# DUCO_Miner_10D.net
KiCad netlist of a schematic drawn in EAGLE
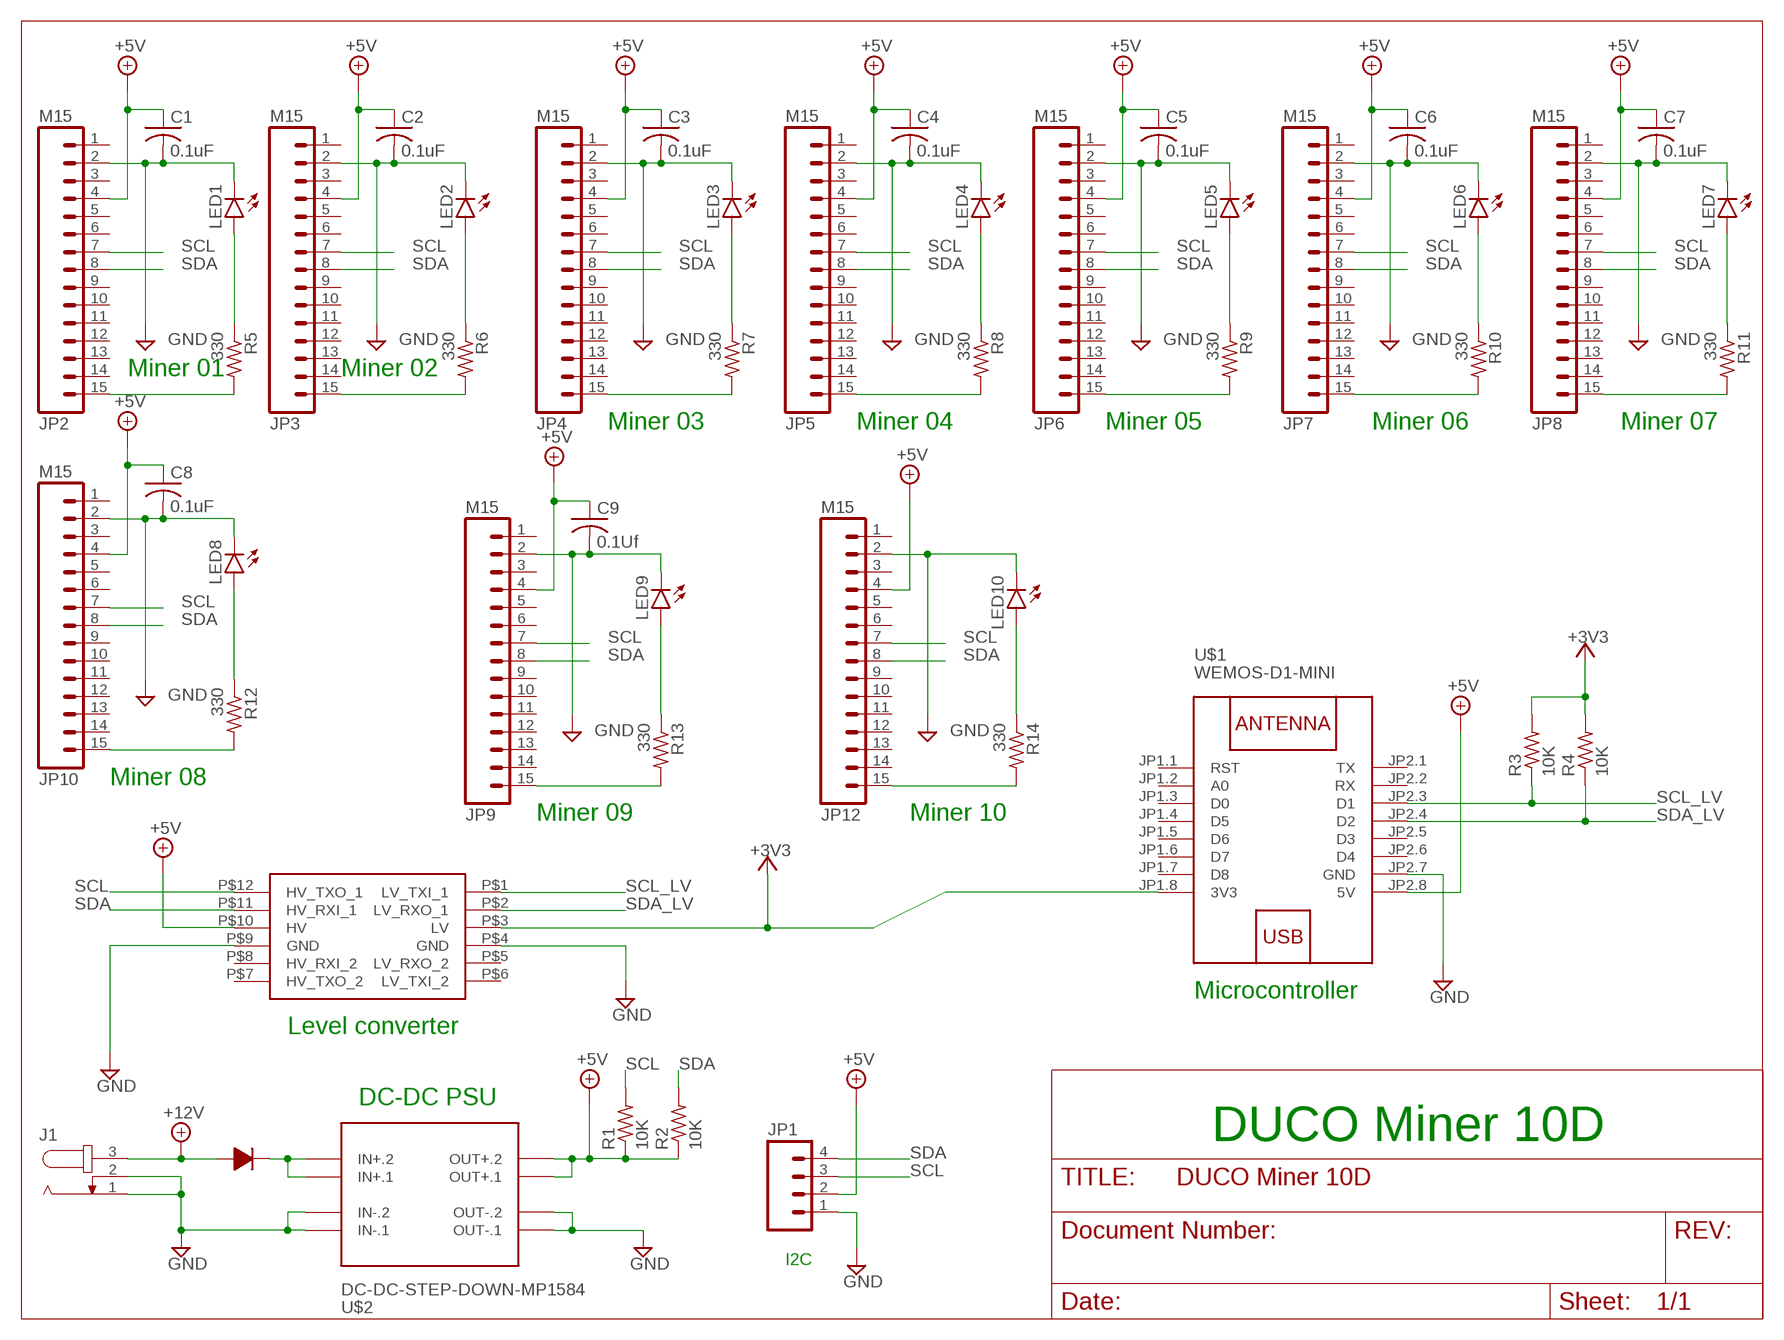
[diagram p0: schematic, sheet 1]

(export (version "E")
  (design (tool "Eeschema 10.0.6"))
  (components
    (comp (ref "C1")
      (value "0.1uF")
      (footprint "eagle-import:C025-025X050")
      (libsource (lib "eagle-import") (part "C-US025-025X050"))
    )
    (comp (ref "C2")
      (value "0.1uF")
      (footprint "eagle-import:C025-025X050")
      (libsource (lib "eagle-import") (part "C-US025-025X050"))
    )
    (comp (ref "C3")
      (value "0.1uF")
      (footprint "eagle-import:C025-025X050")
      (libsource (lib "eagle-import") (part "C-US025-025X050"))
    )
    (comp (ref "C4")
      (value "0.1uF")
      (footprint "eagle-import:C025-025X050")
      (libsource (lib "eagle-import") (part "C-US025-025X050"))
    )
    (comp (ref "C5")
      (value "0.1uF")
      (footprint "eagle-import:C025-025X050")
      (libsource (lib "eagle-import") (part "C-US025-025X050"))
    )
    (comp (ref "C6")
      (value "0.1uF")
      (footprint "eagle-import:C025-025X050")
      (libsource (lib "eagle-import") (part "C-US025-025X050"))
    )
    (comp (ref "C7")
      (value "0.1uF")
      (footprint "eagle-import:C025-025X050")
      (libsource (lib "eagle-import") (part "C-US025-025X050"))
    )
    (comp (ref "C8")
      (value "0.1uF")
      (footprint "eagle-import:C025-025X050")
      (libsource (lib "eagle-import") (part "C-US025-025X050"))
    )
    (comp (ref "C9")
      (value "0.1Uf")
      (footprint "eagle-import:C025-025X050")
      (libsource (lib "eagle-import") (part "C-US025-025X050"))
    )
    (comp (ref "J1")
      (value "JACK-PLUG1")
      (footprint "eagle-import:SPC4078")
      (libsource (lib "eagle-import") (part "JACK-PLUG1"))
    )
    (comp (ref "JP1")
      (value "M04PTH")
      (footprint "eagle-import:1X04")
      (libsource (lib "eagle-import") (part "M04PTH"))
    )
    (comp (ref "JP2")
      (value "M15")
      (footprint "eagle-import:1X15")
      (libsource (lib "eagle-import") (part "M15"))
    )
    (comp (ref "JP3")
      (value "M15")
      (footprint "eagle-import:1X15")
      (libsource (lib "eagle-import") (part "M15"))
    )
    (comp (ref "JP4")
      (value "M15")
      (footprint "eagle-import:1X15")
      (libsource (lib "eagle-import") (part "M15"))
    )
    (comp (ref "JP5")
      (value "M15")
      (footprint "eagle-import:1X15")
      (libsource (lib "eagle-import") (part "M15"))
    )
    (comp (ref "JP6")
      (value "M15")
      (footprint "eagle-import:1X15")
      (libsource (lib "eagle-import") (part "M15"))
    )
    (comp (ref "JP7")
      (value "M15")
      (footprint "eagle-import:1X15")
      (libsource (lib "eagle-import") (part "M15"))
    )
    (comp (ref "JP8")
      (value "M15")
      (footprint "eagle-import:1X15")
      (libsource (lib "eagle-import") (part "M15"))
    )
    (comp (ref "JP9")
      (value "M15")
      (footprint "eagle-import:1X15")
      (libsource (lib "eagle-import") (part "M15"))
    )
    (comp (ref "JP10")
      (value "M15")
      (footprint "eagle-import:1X15")
      (libsource (lib "eagle-import") (part "M15"))
    )
    (comp (ref "JP12")
      (value "M15")
      (footprint "eagle-import:1X15")
      (libsource (lib "eagle-import") (part "M15"))
    )
    (comp (ref "LED1")
      (value "LED3MM")
      (footprint "eagle-import:LED3MM")
      (libsource (lib "eagle-import") (part "LED3MM"))
    )
    (comp (ref "LED2")
      (value "LED3MM")
      (footprint "eagle-import:LED3MM")
      (libsource (lib "eagle-import") (part "LED3MM"))
    )
    (comp (ref "LED3")
      (value "LED3MM")
      (footprint "eagle-import:LED3MM")
      (libsource (lib "eagle-import") (part "LED3MM"))
    )
    (comp (ref "LED4")
      (value "LED3MM")
      (footprint "eagle-import:LED3MM")
      (libsource (lib "eagle-import") (part "LED3MM"))
    )
    (comp (ref "LED5")
      (value "LED3MM")
      (footprint "eagle-import:LED3MM")
      (libsource (lib "eagle-import") (part "LED3MM"))
    )
    (comp (ref "LED6")
      (value "LED3MM")
      (footprint "eagle-import:LED3MM")
      (libsource (lib "eagle-import") (part "LED3MM"))
    )
    (comp (ref "LED7")
      (value "LED3MM")
      (footprint "eagle-import:LED3MM")
      (libsource (lib "eagle-import") (part "LED3MM"))
    )
    (comp (ref "LED8")
      (value "LED3MM")
      (footprint "eagle-import:LED3MM")
      (libsource (lib "eagle-import") (part "LED3MM"))
    )
    (comp (ref "LED9")
      (value "LED3MM")
      (footprint "eagle-import:LED3MM")
      (libsource (lib "eagle-import") (part "LED3MM"))
    )
    (comp (ref "LED10")
      (value "LED3MM")
      (footprint "eagle-import:LED3MM")
      (libsource (lib "eagle-import") (part "LED3MM"))
    )
    (comp (ref "R1")
      (value "10K")
      (footprint "eagle-import:0204_7")
      (libsource (lib "eagle-import") (part "rcl_334_R-US_0204/7"))
    )
    (comp (ref "R2")
      (value "10K")
      (footprint "eagle-import:0204_7")
      (libsource (lib "eagle-import") (part "rcl_334_R-US_0204/7"))
    )
    (comp (ref "R3")
      (value "10K")
      (footprint "eagle-import:0204_7")
      (libsource (lib "eagle-import") (part "rcl_334_R-US_0204/7"))
    )
    (comp (ref "R4")
      (value "10K")
      (footprint "eagle-import:0204_7")
      (libsource (lib "eagle-import") (part "rcl_334_R-US_0204/7"))
    )
    (comp (ref "R5")
      (value "330")
      (footprint "eagle-import:0204_7")
      (libsource (lib "eagle-import") (part "R-US_0204/7"))
    )
    (comp (ref "R6")
      (value "330")
      (footprint "eagle-import:0204_7")
      (libsource (lib "eagle-import") (part "R-US_0204/7"))
    )
    (comp (ref "R7")
      (value "330")
      (footprint "eagle-import:0204_7")
      (libsource (lib "eagle-import") (part "R-US_0204/7"))
    )
    (comp (ref "R8")
      (value "330")
      (footprint "eagle-import:0204_7")
      (libsource (lib "eagle-import") (part "R-US_0204/7"))
    )
    (comp (ref "R9")
      (value "330")
      (footprint "eagle-import:0204_7")
      (libsource (lib "eagle-import") (part "R-US_0204/7"))
    )
    (comp (ref "R10")
      (value "330")
      (footprint "eagle-import:0204_7")
      (libsource (lib "eagle-import") (part "R-US_0204/7"))
    )
    (comp (ref "R11")
      (value "330")
      (footprint "eagle-import:0204_7")
      (libsource (lib "eagle-import") (part "R-US_0204/7"))
    )
    (comp (ref "R12")
      (value "330")
      (footprint "eagle-import:0204_7")
      (libsource (lib "eagle-import") (part "R-US_0204/7"))
    )
    (comp (ref "R13")
      (value "330")
      (footprint "eagle-import:0204_7")
      (libsource (lib "eagle-import") (part "R-US_0204/7"))
    )
    (comp (ref "R14")
      (value "330")
      (footprint "eagle-import:0204_7")
      (libsource (lib "eagle-import") (part "R-US_0204/7"))
    )
    (comp (ref "U$1")
      (value "WEMOS-D1-MINI")
      (footprint "eagle-import:WEMOS-D1-MINI")
      (libsource (lib "eagle-import") (part "WEMOS-D1-MINI"))
    )
    (comp (ref "U$2")
      (value "DC-DC-STEP-DOWN-MP1584")
      (footprint "eagle-import:DC-DC-STEP-DOWN-MP1584")
      (libsource (lib "eagle-import") (part "DC-DC-STEP-DOWN-MP1584"))
    )
    (comp (ref "U$3")
      (value "LOGIC_LEVEL_CONVERTER")
      (footprint "eagle-import:LOGIC_LEVEL_CONVERTER")
      (libsource (lib "eagle-import") (part "LOGIC_LEVEL_CONVERTER"))
    )
    (comp (ref "U$4")
      (value "1N4001")
      (footprint "eagle-import:DIODE-12.70")
      (libsource (lib "eagle-import") (part "1N4001"))
    )
  )
  (nets
    (net (code "1") (name "+3V3") (class "Default")
      (node (ref "R3") (pin "2") (pinfunction "2_2") (pintype "passive"))
      (node (ref "R4") (pin "2") (pinfunction "2_2") (pintype "passive"))
      (node (ref "U$1") (pin "JP1.8") (pinfunction "3V3_JP1.8") (pintype "power_in"))
      (node (ref "U$3") (pin "P$3") (pinfunction "LV_P$3") (pintype "bidirectional"))
    )
    (net (code "2") (name "+5V") (class "Default")
      (node (ref "C1") (pin "1") (pinfunction "1_1") (pintype "passive"))
      (node (ref "C2") (pin "1") (pinfunction "1_1") (pintype "passive"))
      (node (ref "C3") (pin "1") (pinfunction "1_1") (pintype "passive"))
      (node (ref "C4") (pin "1") (pinfunction "1_1") (pintype "passive"))
      (node (ref "C5") (pin "1") (pinfunction "1_1") (pintype "passive"))
      (node (ref "C6") (pin "1") (pinfunction "1_1") (pintype "passive"))
      (node (ref "C7") (pin "1") (pinfunction "1_1") (pintype "passive"))
      (node (ref "C8") (pin "1") (pinfunction "1_1") (pintype "passive"))
      (node (ref "C9") (pin "1") (pinfunction "1_1") (pintype "passive"))
      (node (ref "JP1") (pin "2") (pinfunction "2_2") (pintype "passive"))
      (node (ref "JP10") (pin "4") (pinfunction "4_4") (pintype "passive"))
      (node (ref "JP12") (pin "4") (pinfunction "4_4") (pintype "passive"))
      (node (ref "JP2") (pin "4") (pinfunction "4_4") (pintype "passive"))
      (node (ref "JP3") (pin "4") (pinfunction "4_4") (pintype "passive"))
      (node (ref "JP4") (pin "4") (pinfunction "4_4") (pintype "passive"))
      (node (ref "JP5") (pin "4") (pinfunction "4_4") (pintype "passive"))
      (node (ref "JP6") (pin "4") (pinfunction "4_4") (pintype "passive"))
      (node (ref "JP7") (pin "4") (pinfunction "4_4") (pintype "passive"))
      (node (ref "JP8") (pin "4") (pinfunction "4_4") (pintype "passive"))
      (node (ref "JP9") (pin "4") (pinfunction "4_4") (pintype "passive"))
      (node (ref "R1") (pin "1") (pinfunction "1_1") (pintype "passive"))
      (node (ref "R2") (pin "1") (pinfunction "1_1") (pintype "passive"))
      (node (ref "U$1") (pin "JP2.8") (pinfunction "5V_JP2.8") (pintype "power_in"))
      (node (ref "U$2") (pin "OUT+.1") (pinfunction "OUT+.1_OUT+.1") (pintype "bidirectional"))
      (node (ref "U$2") (pin "OUT+.2") (pinfunction "OUT+.2_OUT+.2") (pintype "bidirectional"))
      (node (ref "U$3") (pin "P$10") (pinfunction "HV_P$10") (pintype "bidirectional"))
    )
    (net (code "3") (name "+12V") (class "Default")
      (node (ref "J1") (pin "3") (pinfunction "3_3") (pintype "passive"))
      (node (ref "U$4") (pin "P$1") (pinfunction "P$1_P$1") (pintype "passive"))
    )
    (net (code "4") (name "/SCL") (class "Default")
      (node (ref "JP1") (pin "3") (pinfunction "3_3") (pintype "passive"))
      (node (ref "JP10") (pin "7") (pinfunction "7_7") (pintype "passive"))
      (node (ref "JP12") (pin "7") (pinfunction "7_7") (pintype "passive"))
      (node (ref "JP2") (pin "7") (pinfunction "7_7") (pintype "passive"))
      (node (ref "JP3") (pin "7") (pinfunction "7_7") (pintype "passive"))
      (node (ref "JP4") (pin "7") (pinfunction "7_7") (pintype "passive"))
      (node (ref "JP5") (pin "7") (pinfunction "7_7") (pintype "passive"))
      (node (ref "JP6") (pin "7") (pinfunction "7_7") (pintype "passive"))
      (node (ref "JP7") (pin "7") (pinfunction "7_7") (pintype "passive"))
      (node (ref "JP8") (pin "7") (pinfunction "7_7") (pintype "passive"))
      (node (ref "JP9") (pin "7") (pinfunction "7_7") (pintype "passive"))
      (node (ref "R1") (pin "2") (pinfunction "2_2") (pintype "passive"))
      (node (ref "U$3") (pin "P$12") (pinfunction "HV_TXO_1_P$12") (pintype "bidirectional"))
    )
    (net (code "5") (name "/SCL_LV") (class "Default")
      (node (ref "R3") (pin "1") (pinfunction "1_1") (pintype "passive"))
      (node (ref "U$1") (pin "JP2.3") (pinfunction "D1_JP2.3") (pintype "bidirectional"))
      (node (ref "U$3") (pin "P$1") (pinfunction "LV_TXI_1_P$1") (pintype "bidirectional"))
    )
    (net (code "6") (name "/SDA") (class "Default")
      (node (ref "JP1") (pin "4") (pinfunction "4_4") (pintype "passive"))
      (node (ref "JP10") (pin "8") (pinfunction "8_8") (pintype "passive"))
      (node (ref "JP12") (pin "8") (pinfunction "8_8") (pintype "passive"))
      (node (ref "JP2") (pin "8") (pinfunction "8_8") (pintype "passive"))
      (node (ref "JP3") (pin "8") (pinfunction "8_8") (pintype "passive"))
      (node (ref "JP4") (pin "8") (pinfunction "8_8") (pintype "passive"))
      (node (ref "JP5") (pin "8") (pinfunction "8_8") (pintype "passive"))
      (node (ref "JP6") (pin "8") (pinfunction "8_8") (pintype "passive"))
      (node (ref "JP7") (pin "8") (pinfunction "8_8") (pintype "passive"))
      (node (ref "JP8") (pin "8") (pinfunction "8_8") (pintype "passive"))
      (node (ref "JP9") (pin "8") (pinfunction "8_8") (pintype "passive"))
      (node (ref "R2") (pin "2") (pinfunction "2_2") (pintype "passive"))
      (node (ref "U$3") (pin "P$11") (pinfunction "HV_RXI_1_P$11") (pintype "bidirectional"))
    )
    (net (code "7") (name "/SDA_LV") (class "Default")
      (node (ref "R4") (pin "1") (pinfunction "1_1") (pintype "passive"))
      (node (ref "U$1") (pin "JP2.4") (pinfunction "D2_JP2.4") (pintype "bidirectional"))
      (node (ref "U$3") (pin "P$2") (pinfunction "LV_RXO_1_P$2") (pintype "bidirectional"))
    )
    (net (code "8") (name "GND") (class "Default")
      (node (ref "C1") (pin "2") (pinfunction "2_2") (pintype "passive"))
      (node (ref "C2") (pin "2") (pinfunction "2_2") (pintype "passive"))
      (node (ref "C3") (pin "2") (pinfunction "2_2") (pintype "passive"))
      (node (ref "C4") (pin "2") (pinfunction "2_2") (pintype "passive"))
      (node (ref "C5") (pin "2") (pinfunction "2_2") (pintype "passive"))
      (node (ref "C6") (pin "2") (pinfunction "2_2") (pintype "passive"))
      (node (ref "C7") (pin "2") (pinfunction "2_2") (pintype "passive"))
      (node (ref "C8") (pin "2") (pinfunction "2_2") (pintype "passive"))
      (node (ref "C9") (pin "2") (pinfunction "2_2") (pintype "passive"))
      (node (ref "J1") (pin "1") (pinfunction "1_1") (pintype "passive"))
      (node (ref "J1") (pin "2") (pinfunction "2_2") (pintype "passive"))
      (node (ref "JP1") (pin "1") (pinfunction "1_1") (pintype "passive"))
      (node (ref "JP10") (pin "2") (pinfunction "2_2") (pintype "passive"))
      (node (ref "JP12") (pin "2") (pinfunction "2_2") (pintype "passive"))
      (node (ref "JP2") (pin "2") (pinfunction "2_2") (pintype "passive"))
      (node (ref "JP3") (pin "2") (pinfunction "2_2") (pintype "passive"))
      (node (ref "JP4") (pin "2") (pinfunction "2_2") (pintype "passive"))
      (node (ref "JP5") (pin "2") (pinfunction "2_2") (pintype "passive"))
      (node (ref "JP6") (pin "2") (pinfunction "2_2") (pintype "passive"))
      (node (ref "JP7") (pin "2") (pinfunction "2_2") (pintype "passive"))
      (node (ref "JP8") (pin "2") (pinfunction "2_2") (pintype "passive"))
      (node (ref "JP9") (pin "2") (pinfunction "2_2") (pintype "passive"))
      (node (ref "LED1") (pin "K") (pinfunction "C_K") (pintype "passive"))
      (node (ref "LED10") (pin "K") (pinfunction "C_K") (pintype "passive"))
      (node (ref "LED2") (pin "K") (pinfunction "C_K") (pintype "passive"))
      (node (ref "LED3") (pin "K") (pinfunction "C_K") (pintype "passive"))
      (node (ref "LED4") (pin "K") (pinfunction "C_K") (pintype "passive"))
      (node (ref "LED5") (pin "K") (pinfunction "C_K") (pintype "passive"))
      (node (ref "LED6") (pin "K") (pinfunction "C_K") (pintype "passive"))
      (node (ref "LED7") (pin "K") (pinfunction "C_K") (pintype "passive"))
      (node (ref "LED8") (pin "K") (pinfunction "C_K") (pintype "passive"))
      (node (ref "LED9") (pin "K") (pinfunction "C_K") (pintype "passive"))
      (node (ref "U$1") (pin "JP2.7") (pinfunction "GND_JP2.7") (pintype "power_in"))
      (node (ref "U$2") (pin "IN-.1") (pinfunction "IN-.1_IN-.1") (pintype "bidirectional"))
      (node (ref "U$2") (pin "IN-.2") (pinfunction "IN-.2_IN-.2") (pintype "bidirectional"))
      (node (ref "U$2") (pin "OUT-.1") (pinfunction "OUT-.1_OUT-.1") (pintype "bidirectional"))
      (node (ref "U$2") (pin "OUT-.2") (pinfunction "OUT-.2_OUT-.2") (pintype "bidirectional"))
      (node (ref "U$3") (pin "P$4") (pinfunction "GND_P$4") (pintype "bidirectional"))
      (node (ref "U$3") (pin "P$9") (pinfunction "GND_P$9") (pintype "bidirectional"))
    )
    (net (code "9") (name "Net-(JP2-Pad15)") (class "Default")
      (node (ref "JP2") (pin "15") (pinfunction "15_15") (pintype "passive"))
      (node (ref "R5") (pin "2") (pinfunction "2_2") (pintype "passive"))
    )
    (net (code "10") (name "Net-(JP3-Pad15)") (class "Default")
      (node (ref "JP3") (pin "15") (pinfunction "15_15") (pintype "passive"))
      (node (ref "R6") (pin "2") (pinfunction "2_2") (pintype "passive"))
    )
    (net (code "11") (name "Net-(JP4-Pad15)") (class "Default")
      (node (ref "JP4") (pin "15") (pinfunction "15_15") (pintype "passive"))
      (node (ref "R7") (pin "2") (pinfunction "2_2") (pintype "passive"))
    )
    (net (code "12") (name "Net-(JP5-Pad15)") (class "Default")
      (node (ref "JP5") (pin "15") (pinfunction "15_15") (pintype "passive"))
      (node (ref "R8") (pin "2") (pinfunction "2_2") (pintype "passive"))
    )
    (net (code "13") (name "Net-(JP6-Pad15)") (class "Default")
      (node (ref "JP6") (pin "15") (pinfunction "15_15") (pintype "passive"))
      (node (ref "R9") (pin "2") (pinfunction "2_2") (pintype "passive"))
    )
    (net (code "14") (name "Net-(JP7-Pad15)") (class "Default")
      (node (ref "JP7") (pin "15") (pinfunction "15_15") (pintype "passive"))
      (node (ref "R10") (pin "2") (pinfunction "2_2") (pintype "passive"))
    )
    (net (code "15") (name "Net-(JP8-Pad15)") (class "Default")
      (node (ref "JP8") (pin "15") (pinfunction "15_15") (pintype "passive"))
      (node (ref "R11") (pin "2") (pinfunction "2_2") (pintype "passive"))
    )
    (net (code "16") (name "Net-(JP9-Pad15)") (class "Default")
      (node (ref "JP9") (pin "15") (pinfunction "15_15") (pintype "passive"))
      (node (ref "R13") (pin "2") (pinfunction "2_2") (pintype "passive"))
    )
    (net (code "17") (name "Net-(JP10-Pad15)") (class "Default")
      (node (ref "JP10") (pin "15") (pinfunction "15_15") (pintype "passive"))
      (node (ref "R12") (pin "2") (pinfunction "2_2") (pintype "passive"))
    )
    (net (code "18") (name "Net-(JP12-Pad15)") (class "Default")
      (node (ref "JP12") (pin "15") (pinfunction "15_15") (pintype "passive"))
      (node (ref "R14") (pin "2") (pinfunction "2_2") (pintype "passive"))
    )
    (net (code "19") (name "Net-(LED1-PadA)") (class "Default")
      (node (ref "LED1") (pin "A") (pinfunction "A_A") (pintype "passive"))
      (node (ref "R5") (pin "1") (pinfunction "1_1") (pintype "passive"))
    )
    (net (code "20") (name "Net-(LED2-PadA)") (class "Default")
      (node (ref "LED2") (pin "A") (pinfunction "A_A") (pintype "passive"))
      (node (ref "R6") (pin "1") (pinfunction "1_1") (pintype "passive"))
    )
    (net (code "21") (name "Net-(LED3-PadA)") (class "Default")
      (node (ref "LED3") (pin "A") (pinfunction "A_A") (pintype "passive"))
      (node (ref "R7") (pin "1") (pinfunction "1_1") (pintype "passive"))
    )
    (net (code "22") (name "Net-(LED4-PadA)") (class "Default")
      (node (ref "LED4") (pin "A") (pinfunction "A_A") (pintype "passive"))
      (node (ref "R8") (pin "1") (pinfunction "1_1") (pintype "passive"))
    )
    (net (code "23") (name "Net-(LED5-PadA)") (class "Default")
      (node (ref "LED5") (pin "A") (pinfunction "A_A") (pintype "passive"))
      (node (ref "R9") (pin "1") (pinfunction "1_1") (pintype "passive"))
    )
    (net (code "24") (name "Net-(LED6-PadA)") (class "Default")
      (node (ref "LED6") (pin "A") (pinfunction "A_A") (pintype "passive"))
      (node (ref "R10") (pin "1") (pinfunction "1_1") (pintype "passive"))
    )
    (net (code "25") (name "Net-(LED7-PadA)") (class "Default")
      (node (ref "LED7") (pin "A") (pinfunction "A_A") (pintype "passive"))
      (node (ref "R11") (pin "1") (pinfunction "1_1") (pintype "passive"))
    )
    (net (code "26") (name "Net-(LED8-PadA)") (class "Default")
      (node (ref "LED8") (pin "A") (pinfunction "A_A") (pintype "passive"))
      (node (ref "R12") (pin "1") (pinfunction "1_1") (pintype "passive"))
    )
    (net (code "27") (name "Net-(LED9-PadA)") (class "Default")
      (node (ref "LED9") (pin "A") (pinfunction "A_A") (pintype "passive"))
      (node (ref "R13") (pin "1") (pinfunction "1_1") (pintype "passive"))
    )
    (net (code "28") (name "Net-(LED10-PadA)") (class "Default")
      (node (ref "LED10") (pin "A") (pinfunction "A_A") (pintype "passive"))
      (node (ref "R14") (pin "1") (pinfunction "1_1") (pintype "passive"))
    )
    (net (code "29") (name "Net-(U$2-PadIN+.1)") (class "Default")
      (node (ref "U$2") (pin "IN+.1") (pinfunction "IN+.1_IN+.1") (pintype "bidirectional"))
      (node (ref "U$2") (pin "IN+.2") (pinfunction "IN+.2_IN+.2") (pintype "bidirectional"))
      (node (ref "U$4") (pin "P$2") (pinfunction "P$2_P$2") (pintype "passive"))
    )
    (net (code "30") (name "unconnected-(JP2-Pad1)") (class "Default")
      (node (ref "JP2") (pin "1") (pinfunction "1_1") (pintype "passive"))
    )
    (net (code "31") (name "unconnected-(JP2-Pad3)") (class "Default")
      (node (ref "JP2") (pin "3") (pinfunction "3_3") (pintype "passive"))
    )
    (net (code "32") (name "unconnected-(JP2-Pad5)") (class "Default")
      (node (ref "JP2") (pin "5") (pinfunction "5_5") (pintype "passive"))
    )
    (net (code "33") (name "unconnected-(JP2-Pad6)") (class "Default")
      (node (ref "JP2") (pin "6") (pinfunction "6_6") (pintype "passive"))
    )
    (net (code "34") (name "unconnected-(JP2-Pad9)") (class "Default")
      (node (ref "JP2") (pin "9") (pinfunction "9_9") (pintype "passive"))
    )
    (net (code "35") (name "unconnected-(JP2-Pad10)") (class "Default")
      (node (ref "JP2") (pin "10") (pinfunction "10_10") (pintype "passive"))
    )
    (net (code "36") (name "unconnected-(JP2-Pad11)") (class "Default")
      (node (ref "JP2") (pin "11") (pinfunction "11_11") (pintype "passive"))
    )
    (net (code "37") (name "unconnected-(JP2-Pad12)") (class "Default")
      (node (ref "JP2") (pin "12") (pinfunction "12_12") (pintype "passive"))
    )
    (net (code "38") (name "unconnected-(JP2-Pad13)") (class "Default")
      (node (ref "JP2") (pin "13") (pinfunction "13_13") (pintype "passive"))
    )
    (net (code "39") (name "unconnected-(JP2-Pad14)") (class "Default")
      (node (ref "JP2") (pin "14") (pinfunction "14_14") (pintype "passive"))
    )
    (net (code "40") (name "unconnected-(JP3-Pad1)") (class "Default")
      (node (ref "JP3") (pin "1") (pinfunction "1_1") (pintype "passive"))
    )
    (net (code "41") (name "unconnected-(JP3-Pad3)") (class "Default")
      (node (ref "JP3") (pin "3") (pinfunction "3_3") (pintype "passive"))
    )
    (net (code "42") (name "unconnected-(JP3-Pad5)") (class "Default")
      (node (ref "JP3") (pin "5") (pinfunction "5_5") (pintype "passive"))
    )
    (net (code "43") (name "unconnected-(JP3-Pad6)") (class "Default")
      (node (ref "JP3") (pin "6") (pinfunction "6_6") (pintype "passive"))
    )
    (net (code "44") (name "unconnected-(JP3-Pad9)") (class "Default")
      (node (ref "JP3") (pin "9") (pinfunction "9_9") (pintype "passive"))
    )
    (net (code "45") (name "unconnected-(JP3-Pad10)") (class "Default")
      (node (ref "JP3") (pin "10") (pinfunction "10_10") (pintype "passive"))
    )
    (net (code "46") (name "unconnected-(JP3-Pad11)") (class "Default")
      (node (ref "JP3") (pin "11") (pinfunction "11_11") (pintype "passive"))
    )
    (net (code "47") (name "unconnected-(JP3-Pad12)") (class "Default")
      (node (ref "JP3") (pin "12") (pinfunction "12_12") (pintype "passive"))
    )
    (net (code "48") (name "unconnected-(JP3-Pad13)") (class "Default")
      (node (ref "JP3") (pin "13") (pinfunction "13_13") (pintype "passive"))
    )
    (net (code "49") (name "unconnected-(JP3-Pad14)") (class "Default")
      (node (ref "JP3") (pin "14") (pinfunction "14_14") (pintype "passive"))
    )
    (net (code "50") (name "unconnected-(JP4-Pad1)") (class "Default")
      (node (ref "JP4") (pin "1") (pinfunction "1_1") (pintype "passive"))
    )
    (net (code "51") (name "unconnected-(JP4-Pad3)") (class "Default")
      (node (ref "JP4") (pin "3") (pinfunction "3_3") (pintype "passive"))
    )
    (net (code "52") (name "unconnected-(JP4-Pad5)") (class "Default")
      (node (ref "JP4") (pin "5") (pinfunction "5_5") (pintype "passive"))
    )
    (net (code "53") (name "unconnected-(JP4-Pad6)") (class "Default")
      (node (ref "JP4") (pin "6") (pinfunction "6_6") (pintype "passive"))
    )
    (net (code "54") (name "unconnected-(JP4-Pad9)") (class "Default")
      (node (ref "JP4") (pin "9") (pinfunction "9_9") (pintype "passive"))
    )
    (net (code "55") (name "unconnected-(JP4-Pad10)") (class "Default")
      (node (ref "JP4") (pin "10") (pinfunction "10_10") (pintype "passive"))
    )
    (net (code "56") (name "unconnected-(JP4-Pad11)") (class "Default")
      (node (ref "JP4") (pin "11") (pinfunction "11_11") (pintype "passive"))
    )
    (net (code "57") (name "unconnected-(JP4-Pad12)") (class "Default")
      (node (ref "JP4") (pin "12") (pinfunction "12_12") (pintype "passive"))
    )
    (net (code "58") (name "unconnected-(JP4-Pad13)") (class "Default")
      (node (ref "JP4") (pin "13") (pinfunction "13_13") (pintype "passive"))
    )
    (net (code "59") (name "unconnected-(JP4-Pad14)") (class "Default")
      (node (ref "JP4") (pin "14") (pinfunction "14_14") (pintype "passive"))
    )
    (net (code "60") (name "unconnected-(JP5-Pad1)") (class "Default")
      (node (ref "JP5") (pin "1") (pinfunction "1_1") (pintype "passive"))
    )
    (net (code "61") (name "unconnected-(JP5-Pad3)") (class "Default")
      (node (ref "JP5") (pin "3") (pinfunction "3_3") (pintype "passive"))
    )
    (net (code "62") (name "unconnected-(JP5-Pad5)") (class "Default")
      (node (ref "JP5") (pin "5") (pinfunction "5_5") (pintype "passive"))
    )
    (net (code "63") (name "unconnected-(JP5-Pad6)") (class "Default")
      (node (ref "JP5") (pin "6") (pinfunction "6_6") (pintype "passive"))
    )
    (net (code "64") (name "unconnected-(JP5-Pad9)") (class "Default")
      (node (ref "JP5") (pin "9") (pinfunction "9_9") (pintype "passive"))
    )
    (net (code "65") (name "unconnected-(JP5-Pad10)") (class "Default")
      (node (ref "JP5") (pin "10") (pinfunction "10_10") (pintype "passive"))
    )
    (net (code "66") (name "unconnected-(JP5-Pad11)") (class "Default")
      (node (ref "JP5") (pin "11") (pinfunction "11_11") (pintype "passive"))
    )
    (net (code "67") (name "unconnected-(JP5-Pad12)") (class "Default")
      (node (ref "JP5") (pin "12") (pinfunction "12_12") (pintype "passive"))
    )
    (net (code "68") (name "unconnected-(JP5-Pad13)") (class "Default")
      (node (ref "JP5") (pin "13") (pinfunction "13_13") (pintype "passive"))
    )
    (net (code "69") (name "unconnected-(JP5-Pad14)") (class "Default")
      (node (ref "JP5") (pin "14") (pinfunction "14_14") (pintype "passive"))
    )
    (net (code "70") (name "unconnected-(JP6-Pad1)") (class "Default")
      (node (ref "JP6") (pin "1") (pinfunction "1_1") (pintype "passive"))
    )
    (net (code "71") (name "unconnected-(JP6-Pad3)") (class "Default")
      (node (ref "JP6") (pin "3") (pinfunction "3_3") (pintype "passive"))
    )
    (net (code "72") (name "unconnected-(JP6-Pad5)") (class "Default")
      (node (ref "JP6") (pin "5") (pinfunction "5_5") (pintype "passive"))
    )
    (net (code "73") (name "unconnected-(JP6-Pad6)") (class "Default")
      (node (ref "JP6") (pin "6") (pinfunction "6_6") (pintype "passive"))
    )
    (net (code "74") (name "unconnected-(JP6-Pad9)") (class "Default")
      (node (ref "JP6") (pin "9") (pinfunction "9_9") (pintype "passive"))
    )
    (net (code "75") (name "unconnected-(JP6-Pad10)") (class "Default")
      (node (ref "JP6") (pin "10") (pinfunction "10_10") (pintype "passive"))
    )
    (net (code "76") (name "unconnected-(JP6-Pad11)") (class "Default")
      (node (ref "JP6") (pin "11") (pinfunction "11_11") (pintype "passive"))
    )
    (net (code "77") (name "unconnected-(JP6-Pad12)") (class "Default")
      (node (ref "JP6") (pin "12") (pinfunction "12_12") (pintype "passive"))
    )
    (net (code "78") (name "unconnected-(JP6-Pad13)") (class "Default")
      (node (ref "JP6") (pin "13") (pinfunction "13_13") (pintype "passive"))
    )
    (net (code "79") (name "unconnected-(JP6-Pad14)") (class "Default")
      (node (ref "JP6") (pin "14") (pinfunction "14_14") (pintype "passive"))
    )
    (net (code "80") (name "unconnected-(JP7-Pad1)") (class "Default")
      (node (ref "JP7") (pin "1") (pinfunction "1_1") (pintype "passive"))
    )
    (net (code "81") (name "unconnected-(JP7-Pad3)") (class "Default")
      (node (ref "JP7") (pin "3") (pinfunction "3_3") (pintype "passive"))
    )
    (net (code "82") (name "unconnected-(JP7-Pad5)") (class "Default")
      (node (ref "JP7") (pin "5") (pinfunction "5_5") (pintype "passive"))
    )
    (net (code "83") (name "unconnected-(JP7-Pad6)") (class "Default")
      (node (ref "JP7") (pin "6") (pinfunction "6_6") (pintype "passive"))
    )
    (net (code "84") (name "unconnected-(JP7-Pad9)") (class "Default")
      (node (ref "JP7") (pin "9") (pinfunction "9_9") (pintype "passive"))
    )
    (net (code "85") (name "unconnected-(JP7-Pad10)") (class "Default")
      (node (ref "JP7") (pin "10") (pinfunction "10_10") (pintype "passive"))
    )
    (net (code "86") (name "unconnected-(JP7-Pad11)") (class "Default")
      (node (ref "JP7") (pin "11") (pinfunction "11_11") (pintype "passive"))
    )
    (net (code "87") (name "unconnected-(JP7-Pad12)") (class "Default")
      (node (ref "JP7") (pin "12") (pinfunction "12_12") (pintype "passive"))
    )
    (net (code "88") (name "unconnected-(JP7-Pad13)") (class "Default")
      (node (ref "JP7") (pin "13") (pinfunction "13_13") (pintype "passive"))
    )
    (net (code "89") (name "unconnected-(JP7-Pad14)") (class "Default")
      (node (ref "JP7") (pin "14") (pinfunction "14_14") (pintype "passive"))
    )
    (net (code "90") (name "unconnected-(JP8-Pad1)") (class "Default")
      (node (ref "JP8") (pin "1") (pinfunction "1_1") (pintype "passive"))
    )
    (net (code "91") (name "unconnected-(JP8-Pad3)") (class "Default")
      (node (ref "JP8") (pin "3") (pinfunction "3_3") (pintype "passive"))
    )
    (net (code "92") (name "unconnected-(JP8-Pad5)") (class "Default")
      (node (ref "JP8") (pin "5") (pinfunction "5_5") (pintype "passive"))
    )
    (net (code "93") (name "unconnected-(JP8-Pad6)") (class "Default")
      (node (ref "JP8") (pin "6") (pinfunction "6_6") (pintype "passive"))
    )
    (net (code "94") (name "unconnected-(JP8-Pad9)") (class "Default")
      (node (ref "JP8") (pin "9") (pinfunction "9_9") (pintype "passive"))
    )
    (net (code "95") (name "unconnected-(JP8-Pad10)") (class "Default")
      (node (ref "JP8") (pin "10") (pinfunction "10_10") (pintype "passive"))
    )
    (net (code "96") (name "unconnected-(JP8-Pad11)") (class "Default")
      (node (ref "JP8") (pin "11") (pinfunction "11_11") (pintype "passive"))
    )
    (net (code "97") (name "unconnected-(JP8-Pad12)") (class "Default")
      (node (ref "JP8") (pin "12") (pinfunction "12_12") (pintype "passive"))
    )
    (net (code "98") (name "unconnected-(JP8-Pad13)") (class "Default")
      (node (ref "JP8") (pin "13") (pinfunction "13_13") (pintype "passive"))
    )
    (net (code "99") (name "unconnected-(JP8-Pad14)") (class "Default")
      (node (ref "JP8") (pin "14") (pinfunction "14_14") (pintype "passive"))
    )
    (net (code "100") (name "unconnected-(JP9-Pad1)") (class "Default")
      (node (ref "JP9") (pin "1") (pinfunction "1_1") (pintype "passive"))
    )
    (net (code "101") (name "unconnected-(JP9-Pad3)") (class "Default")
      (node (ref "JP9") (pin "3") (pinfunction "3_3") (pintype "passive"))
    )
    (net (code "102") (name "unconnected-(JP9-Pad5)") (class "Default")
      (node (ref "JP9") (pin "5") (pinfunction "5_5") (pintype "passive"))
    )
    (net (code "103") (name "unconnected-(JP9-Pad6)") (class "Default")
      (node (ref "JP9") (pin "6") (pinfunction "6_6") (pintype "passive"))
    )
    (net (code "104") (name "unconnected-(JP9-Pad9)") (class "Default")
      (node (ref "JP9") (pin "9") (pinfunction "9_9") (pintype "passive"))
    )
    (net (code "105") (name "unconnected-(JP9-Pad10)") (class "Default")
      (node (ref "JP9") (pin "10") (pinfunction "10_10") (pintype "passive"))
    )
    (net (code "106") (name "unconnected-(JP9-Pad11)") (class "Default")
      (node (ref "JP9") (pin "11") (pinfunction "11_11") (pintype "passive"))
    )
    (net (code "107") (name "unconnected-(JP9-Pad12)") (class "Default")
      (node (ref "JP9") (pin "12") (pinfunction "12_12") (pintype "passive"))
    )
    (net (code "108") (name "unconnected-(JP9-Pad13)") (class "Default")
      (node (ref "JP9") (pin "13") (pinfunction "13_13") (pintype "passive"))
    )
    (net (code "109") (name "unconnected-(JP9-Pad14)") (class "Default")
      (node (ref "JP9") (pin "14") (pinfunction "14_14") (pintype "passive"))
    )
    (net (code "110") (name "unconnected-(JP10-Pad1)") (class "Default")
      (node (ref "JP10") (pin "1") (pinfunction "1_1") (pintype "passive"))
    )
    (net (code "111") (name "unconnected-(JP10-Pad3)") (class "Default")
      (node (ref "JP10") (pin "3") (pinfunction "3_3") (pintype "passive"))
    )
    (net (code "112") (name "unconnected-(JP10-Pad5)") (class "Default")
      (node (ref "JP10") (pin "5") (pinfunction "5_5") (pintype "passive"))
    )
    (net (code "113") (name "unconnected-(JP10-Pad6)") (class "Default")
      (node (ref "JP10") (pin "6") (pinfunction "6_6") (pintype "passive"))
    )
    (net (code "114") (name "unconnected-(JP10-Pad9)") (class "Default")
      (node (ref "JP10") (pin "9") (pinfunction "9_9") (pintype "passive"))
    )
    (net (code "115") (name "unconnected-(JP10-Pad10)") (class "Default")
      (node (ref "JP10") (pin "10") (pinfunction "10_10") (pintype "passive"))
    )
    (net (code "116") (name "unconnected-(JP10-Pad11)") (class "Default")
      (node (ref "JP10") (pin "11") (pinfunction "11_11") (pintype "passive"))
    )
    (net (code "117") (name "unconnected-(JP10-Pad12)") (class "Default")
      (node (ref "JP10") (pin "12") (pinfunction "12_12") (pintype "passive"))
    )
    (net (code "118") (name "unconnected-(JP10-Pad13)") (class "Default")
      (node (ref "JP10") (pin "13") (pinfunction "13_13") (pintype "passive"))
    )
    (net (code "119") (name "unconnected-(JP10-Pad14)") (class "Default")
      (node (ref "JP10") (pin "14") (pinfunction "14_14") (pintype "passive"))
    )
    (net (code "120") (name "unconnected-(JP12-Pad1)") (class "Default")
      (node (ref "JP12") (pin "1") (pinfunction "1_1") (pintype "passive"))
    )
    (net (code "121") (name "unconnected-(JP12-Pad3)") (class "Default")
      (node (ref "JP12") (pin "3") (pinfunction "3_3") (pintype "passive"))
    )
    (net (code "122") (name "unconnected-(JP12-Pad5)") (class "Default")
      (node (ref "JP12") (pin "5") (pinfunction "5_5") (pintype "passive"))
    )
    (net (code "123") (name "unconnected-(JP12-Pad6)") (class "Default")
      (node (ref "JP12") (pin "6") (pinfunction "6_6") (pintype "passive"))
    )
    (net (code "124") (name "unconnected-(JP12-Pad9)") (class "Default")
      (node (ref "JP12") (pin "9") (pinfunction "9_9") (pintype "passive"))
    )
    (net (code "125") (name "unconnected-(JP12-Pad10)") (class "Default")
      (node (ref "JP12") (pin "10") (pinfunction "10_10") (pintype "passive"))
    )
    (net (code "126") (name "unconnected-(JP12-Pad11)") (class "Default")
      (node (ref "JP12") (pin "11") (pinfunction "11_11") (pintype "passive"))
    )
    (net (code "127") (name "unconnected-(JP12-Pad12)") (class "Default")
      (node (ref "JP12") (pin "12") (pinfunction "12_12") (pintype "passive"))
    )
    (net (code "128") (name "unconnected-(JP12-Pad13)") (class "Default")
      (node (ref "JP12") (pin "13") (pinfunction "13_13") (pintype "passive"))
    )
    (net (code "129") (name "unconnected-(JP12-Pad14)") (class "Default")
      (node (ref "JP12") (pin "14") (pinfunction "14_14") (pintype "passive"))
    )
    (net (code "130") (name "unconnected-(U$1-A0-PadJP1.2)") (class "Default")
      (node (ref "U$1") (pin "JP1.2") (pinfunction "A0_JP1.2") (pintype "bidirectional"))
    )
    (net (code "131") (name "unconnected-(U$1-D0-PadJP1.3)") (class "Default")
      (node (ref "U$1") (pin "JP1.3") (pinfunction "D0_JP1.3") (pintype "bidirectional"))
    )
    (net (code "132") (name "unconnected-(U$1-D3-PadJP2.5)") (class "Default")
      (node (ref "U$1") (pin "JP2.5") (pinfunction "D3_JP2.5") (pintype "bidirectional"))
    )
    (net (code "133") (name "unconnected-(U$1-D4-PadJP2.6)") (class "Default")
      (node (ref "U$1") (pin "JP2.6") (pinfunction "D4_JP2.6") (pintype "bidirectional"))
    )
    (net (code "134") (name "unconnected-(U$1-D5-PadJP1.4)") (class "Default")
      (node (ref "U$1") (pin "JP1.4") (pinfunction "D5_JP1.4") (pintype "bidirectional"))
    )
    (net (code "135") (name "unconnected-(U$1-D6-PadJP1.5)") (class "Default")
      (node (ref "U$1") (pin "JP1.5") (pinfunction "D6_JP1.5") (pintype "bidirectional"))
    )
    (net (code "136") (name "unconnected-(U$1-D7-PadJP1.6)") (class "Default")
      (node (ref "U$1") (pin "JP1.6") (pinfunction "D7_JP1.6") (pintype "bidirectional"))
    )
    (net (code "137") (name "unconnected-(U$1-D8-PadJP1.7)") (class "Default")
      (node (ref "U$1") (pin "JP1.7") (pinfunction "D8_JP1.7") (pintype "bidirectional"))
    )
    (net (code "138") (name "unconnected-(U$1-RST-PadJP1.1)") (class "Default")
      (node (ref "U$1") (pin "JP1.1") (pinfunction "RST_JP1.1") (pintype "bidirectional"))
    )
    (net (code "139") (name "unconnected-(U$1-RX-PadJP2.2)") (class "Default")
      (node (ref "U$1") (pin "JP2.2") (pinfunction "RX_JP2.2") (pintype "bidirectional"))
    )
    (net (code "140") (name "unconnected-(U$1-TX-PadJP2.1)") (class "Default")
      (node (ref "U$1") (pin "JP2.1") (pinfunction "TX_JP2.1") (pintype "bidirectional"))
    )
    (net (code "141") (name "unconnected-(U$3-HV_RXI_2-PadP$8)") (class "Default")
      (node (ref "U$3") (pin "P$8") (pinfunction "HV_RXI_2_P$8") (pintype "bidirectional"))
    )
    (net (code "142") (name "unconnected-(U$3-HV_TXO_2-PadP$7)") (class "Default")
      (node (ref "U$3") (pin "P$7") (pinfunction "HV_TXO_2_P$7") (pintype "bidirectional"))
    )
    (net (code "143") (name "unconnected-(U$3-LV_RXO_2-PadP$5)") (class "Default")
      (node (ref "U$3") (pin "P$5") (pinfunction "LV_RXO_2_P$5") (pintype "bidirectional"))
    )
    (net (code "144") (name "unconnected-(U$3-LV_TXI_2-PadP$6)") (class "Default")
      (node (ref "U$3") (pin "P$6") (pinfunction "LV_TXI_2_P$6") (pintype "bidirectional"))
    )
  )
)
